# SimpleAstableMultivibrator.net
KiCad netlist of a schematic drawn in Altium Designer
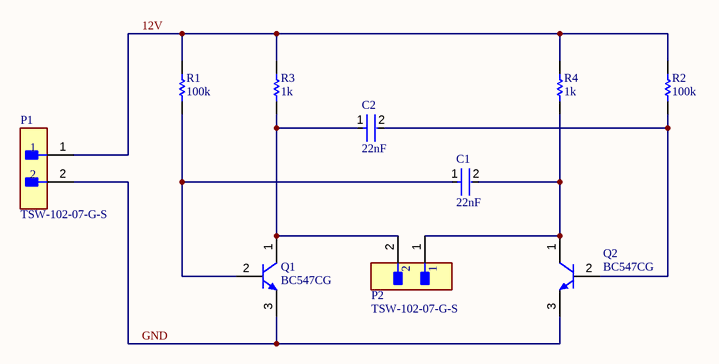
[diagram p0: SimpleAstableMultivibrator.SchDoc]

(export (version "E")
  (design (tool "Eeschema 10.0.6"))
  (components
    (comp (ref "C1")
      (value "22nF")
      (footprint "FP-C0603C-CF-IPC_A")
      (fields (field (name "Comment") "Capacitor 22nF +/-5% 16V 0603"))
      (libsource (lib "Muntakim Rahman") (part "b4654b650e69147ec39a6b967a45e02"))
    )
    (comp (ref "C2")
      (value "22nF")
      (footprint "FP-C0603C-CF-IPC_A")
      (fields (field (name "Comment") "Capacitor 22nF +/-5% 16V 0603"))
      (libsource (lib "Muntakim Rahman") (part "b4654b650e69147ec39a6b967a45e02"))
    )
    (comp (ref "P1")
      (value "TSW-102-07-G-S")
      (footprint "FP-TSW-102-07-G-S-MFG")
      (libsource (lib "Muntakim Rahman") (part "3bc925449376181038e59eaffc5286c"))
    )
    (comp (ref "P2")
      (value "TSW-102-07-G-S")
      (footprint "FP-TSW-102-07-G-S-MFG")
      (libsource (lib "Muntakim Rahman") (part "3bc925449376181038e59eaffc5286c"))
    )
    (comp (ref "Q1")
      (value "BC547CG")
      (footprint "ONSC-TO-92-3-29-11")
      (description "Small Signal Bipolar Transistor, 0.1A I(C), 45V V(BR)CEO, 1-Element, NPN, Silicon, TO-92")
      (libsource (lib "Muntakim Rahman") (part "ONSC-NPN-C1B2E3-3"))
    )
    (comp (ref "Q2")
      (value "BC547CG")
      (footprint "ONSC-TO-92-3-29-11")
      (description "Small Signal Bipolar Transistor, 0.1A I(C), 45V V(BR)CEO, 1-Element, NPN, Silicon, TO-92")
      (libsource (lib "Muntakim Rahman") (part "ONSC-NPN-C1B2E3-3"))
    )
    (comp (ref "R1")
      (value "100k")
      (footprint "RESC2013X70X40ML20T20")
      (fields
        (field (name "TOLERANCE") "5%")
        (field (name "POWER") "125mW")
        (field (name "Comment") "Resistor 100K +/-5% 0805 125 mW")
      )
      (libsource (lib "Muntakim Rahman") (part "RES"))
    )
    (comp (ref "R2")
      (value "100k")
      (footprint "RESC2013X70X40ML20T20")
      (fields
        (field (name "TOLERANCE") "5%")
        (field (name "POWER") "125mW")
        (field (name "Comment") "Resistor 100K +/-5% 0805 125 mW")
      )
      (libsource (lib "Muntakim Rahman") (part "RES"))
    )
    (comp (ref "R3")
      (value "1k")
      (footprint "RESC2013X70X40ML20T20")
      (fields
        (field (name "TOLERANCE") "5%")
        (field (name "POWER") "500mW")
        (field (name "Comment") "Resistor 1K +/-5% 0805 500 mW")
      )
      (libsource (lib "Muntakim Rahman") (part "RES"))
    )
    (comp (ref "R4")
      (value "1k")
      (footprint "RESC2013X70X40ML20T20")
      (fields
        (field (name "TOLERANCE") "5%")
        (field (name "POWER") "500mW")
        (field (name "Comment") "Resistor 1K +/-5% 0805 500 mW")
      )
      (libsource (lib "Muntakim Rahman") (part "RES"))
    )
  )
  (nets
    (net (code "1") (name "/12V") (class "Default")
      (node (ref "P1") (pin "1") (pinfunction "1_1") (pintype "passive"))
      (node (ref "R1") (pin "1") (pinfunction "1_1") (pintype "passive"))
      (node (ref "R2") (pin "1") (pinfunction "1_1") (pintype "passive"))
      (node (ref "R3") (pin "1") (pinfunction "1_1") (pintype "passive"))
      (node (ref "R4") (pin "1") (pinfunction "1_1") (pintype "passive"))
    )
    (net (code "2") (name "/GND") (class "Default")
      (node (ref "P1") (pin "2") (pinfunction "2_2") (pintype "passive"))
      (node (ref "Q1") (pin "3") (pinfunction "E_3") (pintype "passive"))
      (node (ref "Q2") (pin "3") (pinfunction "E_3") (pintype "passive"))
    )
    (net (code "3") (name "Net-(Q1-B)") (class "Default")
      (node (ref "C1") (pin "1") (pinfunction "1_1") (pintype "passive"))
      (node (ref "Q1") (pin "2") (pinfunction "B_2") (pintype "passive"))
      (node (ref "R1") (pin "2") (pinfunction "2_2") (pintype "passive"))
    )
    (net (code "4") (name "Net-(Q1-C)") (class "Default")
      (node (ref "C2") (pin "1") (pinfunction "1_1") (pintype "passive"))
      (node (ref "P2") (pin "2") (pinfunction "2_2") (pintype "passive"))
      (node (ref "Q1") (pin "1") (pinfunction "C_1") (pintype "passive"))
      (node (ref "R3") (pin "2") (pinfunction "2_2") (pintype "passive"))
    )
    (net (code "5") (name "Net-(Q2-B)") (class "Default")
      (node (ref "C2") (pin "2") (pinfunction "2_2") (pintype "passive"))
      (node (ref "Q2") (pin "2") (pinfunction "B_2") (pintype "passive"))
      (node (ref "R2") (pin "2") (pinfunction "2_2") (pintype "passive"))
    )
    (net (code "6") (name "Net-(Q2-C)") (class "Default")
      (node (ref "C1") (pin "2") (pinfunction "2_2") (pintype "passive"))
      (node (ref "P2") (pin "1") (pinfunction "1_1") (pintype "passive"))
      (node (ref "Q2") (pin "1") (pinfunction "C_1") (pintype "passive"))
      (node (ref "R4") (pin "2") (pinfunction "2_2") (pintype "passive"))
    )
  )
)
